# Cuong_Dao_Clock_Led7_23.net
KiCad netlist of a schematic drawn in Altium Designer
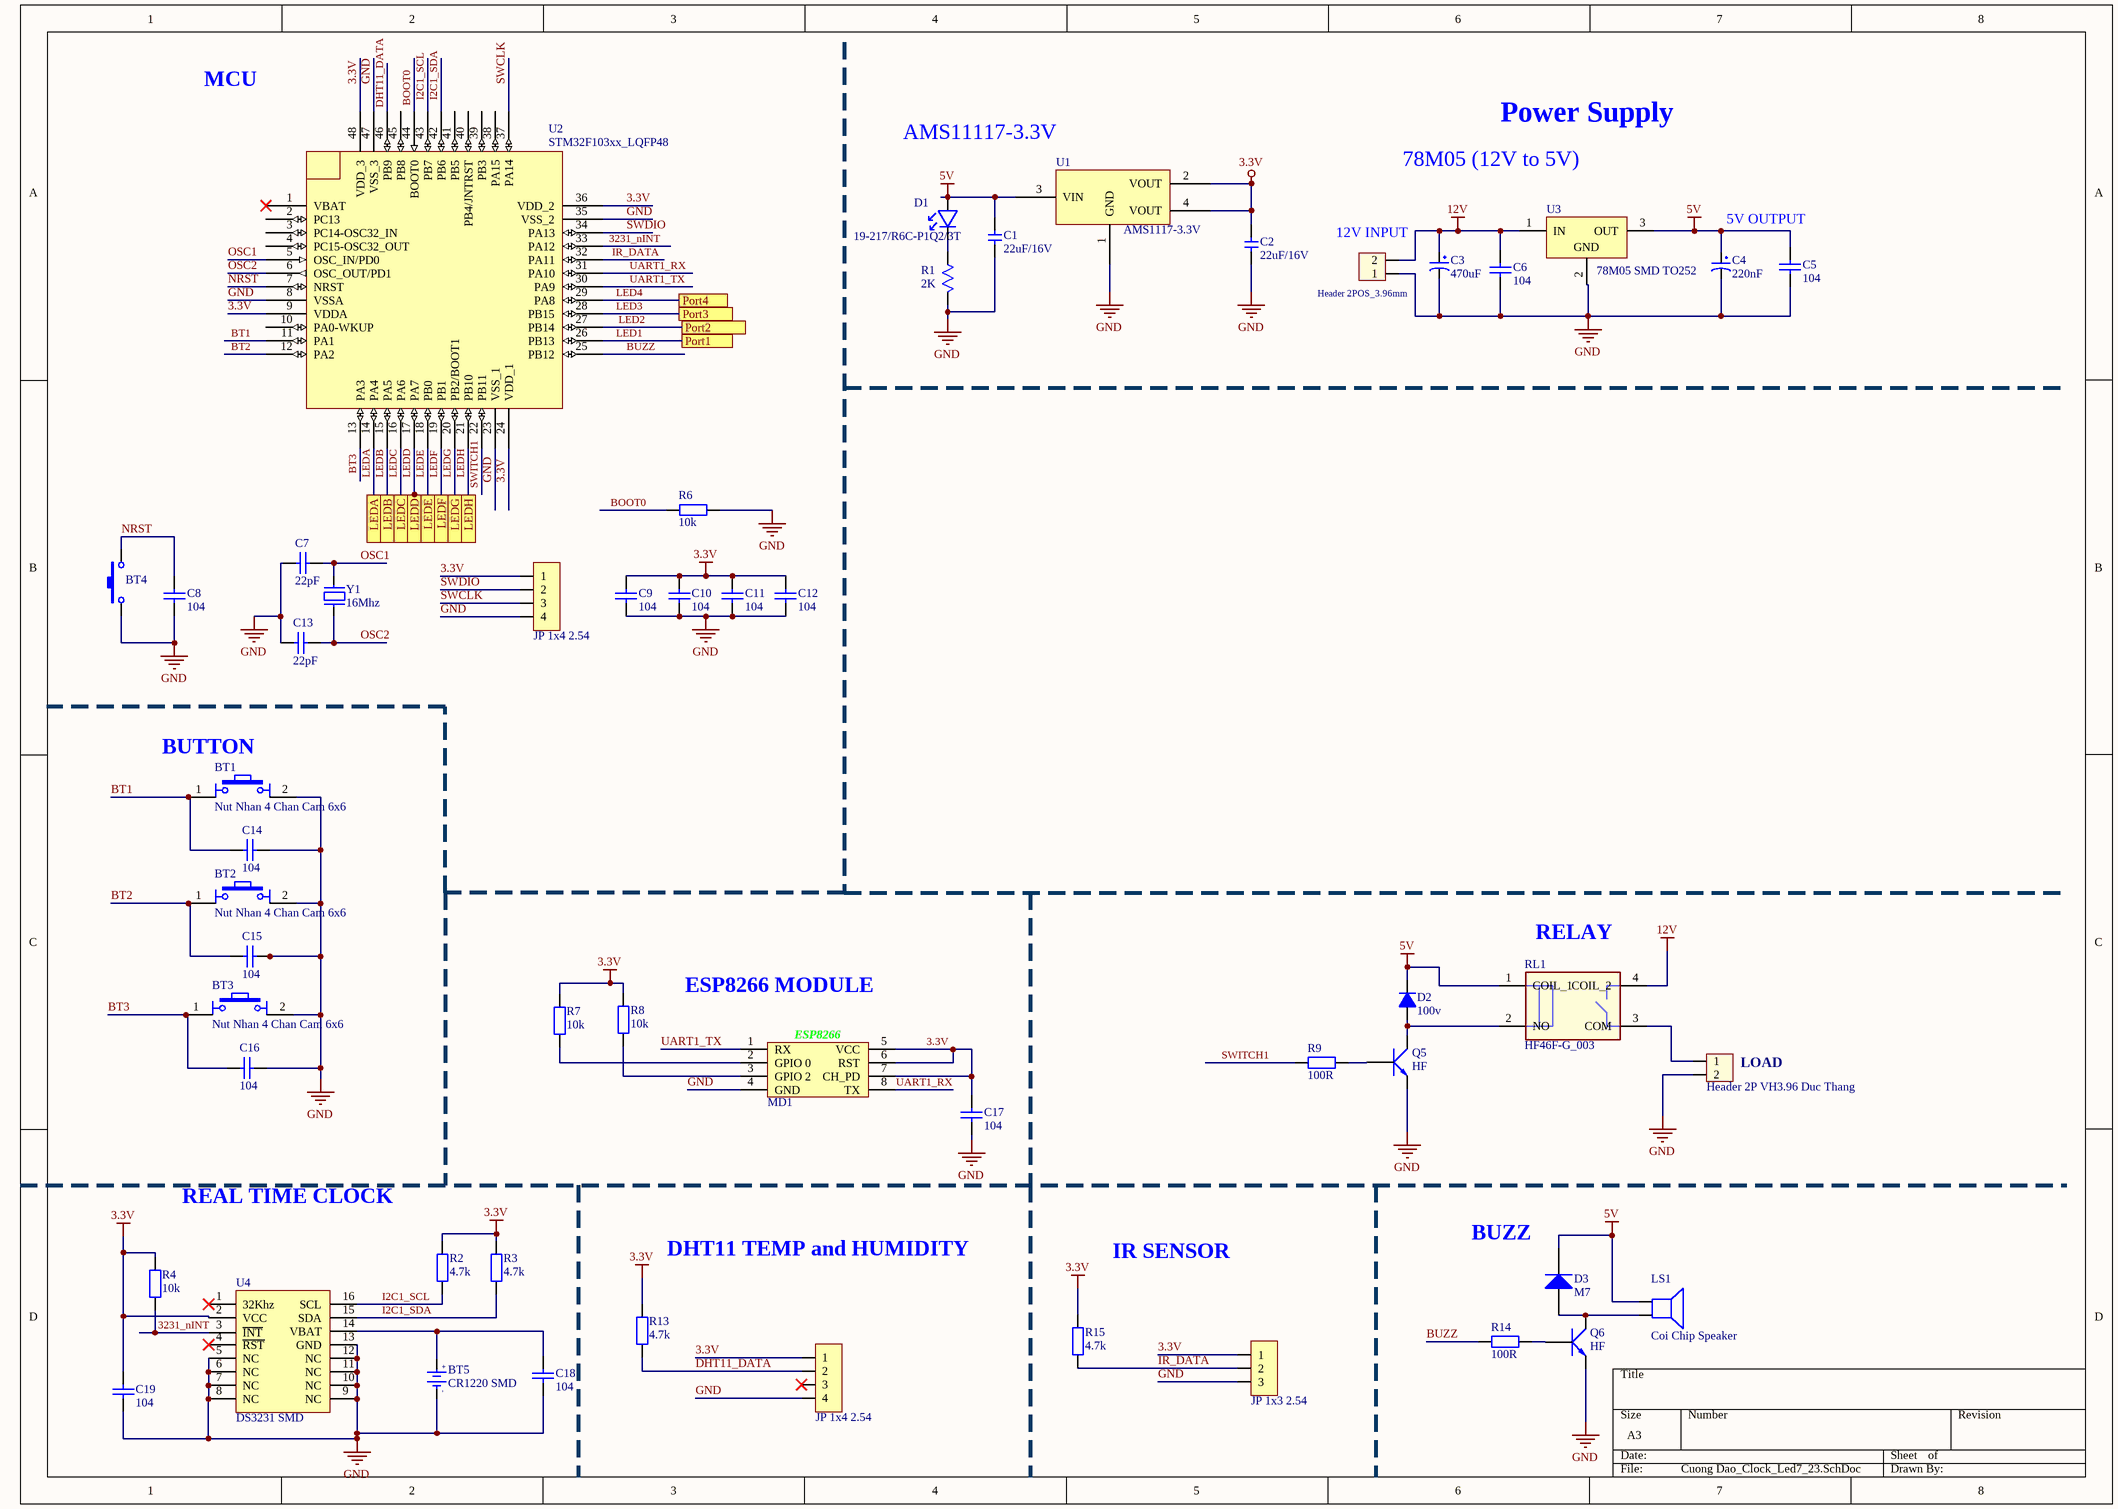
[diagram p0: Cuong Dao_Clock_Led7_23.SchDoc]

(export (version "E")
  (design (tool "Eeschema 10.0.6"))
  (components
    (comp (ref "BT1")
      (value "Nut Nhan 4 Chan Cam 6x6")
      (footprint "Nut Nhan 4 Chan Cam 6x6")
      (description "Nut Nhan 4 Chan 6x6mm")
      (libsource (lib "Altium_Lib_by_KhueNguyenCreator") (part "Nut Nhan 4 Chan Cam 6x6"))
    )
    (comp (ref "BT2")
      (value "Nut Nhan 4 Chan Cam 6x6")
      (footprint "Nut Nhan 4 Chan Cam 6x6")
      (description "Nut Nhan 4 Chan 6x6mm")
      (libsource (lib "Altium_Lib_by_KhueNguyenCreator") (part "Nut Nhan 4 Chan Cam 6x6"))
    )
    (comp (ref "BT3")
      (value "Nut Nhan 4 Chan Cam 6x6")
      (footprint "Nut Nhan 4 Chan Cam 6x6")
      (description "Nut Nhan 4 Chan 6x6mm")
      (libsource (lib "Altium_Lib_by_KhueNguyenCreator") (part "Nut Nhan 4 Chan Cam 6x6"))
    )
    (comp (ref "BT4")
      (value "Nut Nhan 2 Chan SMD 3x6x2.5")
      (footprint "Nut Nhan 2 Chan SMD 3x6x2.5")
      (libsource (lib "Altium_Lib_by_KhueNguyenCreator") (part "Nut Nhan 2 Chan SMD 3x6x2.5"))
    )
    (comp (ref "BT5")
      (value "CR1220 SMD")
      (footprint "DE PIN CR1220")
      (libsource (lib "Altium_Lib_by_KhueNguyenCreator") (part "De pin CR1220 SMD"))
    )
    (comp (ref "C1")
      (value "22uF/16V")
      (footprint "C0603")
      (description "Multilayer Ceramic Capacitors MLCC, SMD/SMT 22uF, 16V, 10%, 0603")
      (libsource (lib "ECA_FAE_Hardware Engineering") (part "C0603"))
    )
    (comp (ref "C2")
      (value "22uF/16V")
      (footprint "C0603")
      (description "Multilayer Ceramic Capacitors MLCC, SMD/SMT 22uF, 16V, 10%, 0603")
      (libsource (lib "ECA_FAE_Hardware Engineering") (part "C0603"))
    )
    (comp (ref "C3")
      (value "470uF")
      (footprint "tu hoa 10mm")
      (description "Cắm")
      (libsource (lib "Altium_Lib_by_KhueNguyenCreator") (part "Tu Hoa 470uF 35V 10x15"))
    )
    (comp (ref "C4")
      (value "220nF")
      (footprint "tu hoa 8mm")
      (description "Cắm")
      (libsource (lib "Altium_Lib_by_KhueNguyenCreator") (part "Tu Hoa 220uF 35V 8x12"))
    )
    (comp (ref "C5")
      (value "104")
      (footprint "tu 1206")
      (description "Dán")
      (libsource (lib "Altium_Lib_by_KhueNguyenCreator") (part "Tu 1206 104 50V 20%"))
    )
    (comp (ref "C6")
      (value "104")
      (footprint "tu 1206")
      (description "Dán")
      (libsource (lib "Altium_Lib_by_KhueNguyenCreator") (part "Tu 1206 104 50V 20%"))
    )
    (comp (ref "C7")
      (value "22pF")
      (footprint "tu 0805")
      (description "Dán")
      (libsource (lib "Altium_Lib_by_KhueNguyenCreator") (part "Tu 0805 22pF 50V 10%"))
    )
    (comp (ref "C8")
      (value "104")
      (footprint "tu 0805")
      (description "Dán")
      (libsource (lib "Altium_Lib_by_KhueNguyenCreator") (part "Tu 0805 104 50V 10%"))
    )
    (comp (ref "C9")
      (value "104")
      (footprint "tu 0805")
      (description "Dán")
      (libsource (lib "Altium_Lib_by_KhueNguyenCreator") (part "Tu 0805 104 50V 10%"))
    )
    (comp (ref "C10")
      (value "104")
      (footprint "tu 0805")
      (description "Dán")
      (libsource (lib "Altium_Lib_by_KhueNguyenCreator") (part "Tu 0805 104 50V 10%"))
    )
    (comp (ref "C11")
      (value "104")
      (footprint "tu 0805")
      (description "Dán")
      (libsource (lib "Altium_Lib_by_KhueNguyenCreator") (part "Tu 0805 104 50V 10%"))
    )
    (comp (ref "C12")
      (value "104")
      (footprint "tu 0805")
      (description "Dán")
      (libsource (lib "Altium_Lib_by_KhueNguyenCreator") (part "Tu 0805 104 50V 10%"))
    )
    (comp (ref "C13")
      (value "22pF")
      (footprint "tu 0805")
      (description "Dán")
      (libsource (lib "Altium_Lib_by_KhueNguyenCreator") (part "Tu 0805 22pF 50V 10%"))
    )
    (comp (ref "C14")
      (value "104")
      (footprint "tu 0805")
      (description "Dán")
      (libsource (lib "Altium_Lib_by_KhueNguyenCreator") (part "Tu 0805 104 50V 10%"))
    )
    (comp (ref "C15")
      (value "104")
      (footprint "tu 0805")
      (description "Dán")
      (libsource (lib "Altium_Lib_by_KhueNguyenCreator") (part "Tu 0805 104 50V 10%"))
    )
    (comp (ref "C16")
      (value "104")
      (footprint "tu 0805")
      (description "Dán")
      (libsource (lib "Altium_Lib_by_KhueNguyenCreator") (part "Tu 0805 104 50V 10%"))
    )
    (comp (ref "C17")
      (value "104")
      (footprint "tu 0805")
      (description "Dán")
      (libsource (lib "Altium_Lib_by_KhueNguyenCreator") (part "Tu 0805 104 50V 10%"))
    )
    (comp (ref "C18")
      (value "104")
      (footprint "tu 0805")
      (description "Dán")
      (libsource (lib "Altium_Lib_by_KhueNguyenCreator") (part "Tu 0805 104 50V 10%"))
    )
    (comp (ref "C19")
      (value "104")
      (footprint "tu 0805")
      (description "Dán")
      (libsource (lib "Altium_Lib_by_KhueNguyenCreator") (part "Tu 0805 104 50V 10%"))
    )
    (comp (ref "D1")
      (value "19-217/R6C-P1Q2/3T")
      (footprint "LED_19-217")
      (description "LED")
      (fields (field (name "PART NUMBER") "19-217/R6C-P1Q2/"))
      (libsource (lib "ICE_Library") (part "LED 19-217"))
    )
    (comp (ref "D2")
      (value "100v")
      (footprint "DIODE 0.5A")
      (description "Cắm")
      (libsource (lib "Altium_Lib_by_KhueNguyenCreator") (part "Diode 1N4148"))
    )
    (comp (ref "D3")
      (value "M7")
      (footprint "DIODE SMA")
      (description "Dán")
      (libsource (lib "Altium_Lib_by_KhueNguyenCreator") (part "Diode M7 ( 4007 )"))
    )
    (comp (ref "H1")
      (value "Header 2POS_3.96mm")
      (footprint "VH3.96M-2")
      (description "Cắm")
      (libsource (lib "Altium_Lib_by_KhueNguyenCreator") (part "Header 2P VH3.96 Duc Thang"))
    )
    (comp (ref "H2")
      (value "Header 2P VH3.96 Duc Thang")
      (footprint "VH3.96M-2")
      (description "Cắm")
      (libsource (lib "") (part "Header 2P VH3.96 Duc Thang_1"))
    )
    (comp (ref "JP1")
      (value "JP 1x4 2.54")
      (footprint "JP 1x4 DT")
      (description "Cắm")
      (libsource (lib "Altium_Lib_by_KhueNguyenCreator") (part "JP 1x4 2.54 Duc Thang"))
    )
    (comp (ref "JP2")
      (value "JP 1x3 2.54")
      (footprint "JP 1x3 CT")
      (description "Cắm")
      (libsource (lib "Altium_Lib_by_KhueNguyenCreator") (part "JP 1x3 2.54 Cai Thang"))
    )
    (comp (ref "JP3")
      (value "JP 1x4 2.54")
      (footprint "JP 1x4 CT")
      (description "Cắm")
      (libsource (lib "Altium_Lib_by_KhueNguyenCreator") (part "JP 1x4 2.54 Cai Thang"))
    )
    (comp (ref "LS1")
      (value "Coi Chip Speaker")
      (footprint "Coi Chip Speacker")
      (description "Còi chip")
      (libsource (lib "Altium_Lib_by_KhueNguyenCreator") (part "Coi Chip Speaker"))
    )
    (comp (ref "MD1")
      (value "ESP8266 Module")
      (footprint "ESP2866 Module")
      (libsource (lib "Altium_Lib_by_KhueNguyenCreator") (part "ESP8266 Module"))
    )
    (comp (ref "Q5")
      (value "HF")
      (footprint "SOT23")
      (description "NPN transistor")
      (libsource (lib "Altium_Lib_by_KhueNguyenCreator") (part "C1815 HF SMD"))
    )
    (comp (ref "Q6")
      (value "HF")
      (footprint "SOT23")
      (description "NPN transistor")
      (libsource (lib "Altium_Lib_by_KhueNguyenCreator") (part "C1815 HF SMD"))
    )
    (comp (ref "R1")
      (value "2K")
      (footprint "RES0603")
      (description "Chip Resistor - Surface Mount 2KΩ ±1% 1/16W 0603 RoHS")
      (libsource (lib "ECA_FAE_Hardware Engineering") (part "R0603"))
    )
    (comp (ref "R2")
      (value "4.7k")
      (footprint "tro smd 0805")
      (description "Dán")
      (libsource (lib "Altium_Lib_by_KhueNguyenCreator") (part "Tro 0805 5% 4.7k"))
    )
    (comp (ref "R3")
      (value "4.7k")
      (footprint "tro smd 0805")
      (description "Dán")
      (libsource (lib "Altium_Lib_by_KhueNguyenCreator") (part "Tro 0805 5% 4.7k"))
    )
    (comp (ref "R4")
      (value "10k")
      (footprint "tro smd 0805")
      (description "Dán")
      (libsource (lib "Altium_Lib_by_KhueNguyenCreator") (part "Tro 0805 5% 10k"))
    )
    (comp (ref "R6")
      (value "10k")
      (footprint "tro smd 0805")
      (description "Dán")
      (libsource (lib "Altium_Lib_by_KhueNguyenCreator") (part "Tro 0805 5% 10k"))
    )
    (comp (ref "R7")
      (value "10k")
      (footprint "tro smd 0805")
      (description "Dán")
      (libsource (lib "Altium_Lib_by_KhueNguyenCreator") (part "Tro 0805 5% 10k"))
    )
    (comp (ref "R8")
      (value "10k")
      (footprint "tro smd 0805")
      (description "Dán")
      (libsource (lib "Altium_Lib_by_KhueNguyenCreator") (part "Tro 0805 5% 10k"))
    )
    (comp (ref "R9")
      (value "100R")
      (footprint "tro smd 0805")
      (description "Dán")
      (libsource (lib "Altium_Lib_by_KhueNguyenCreator") (part "Tro 0805 5% 100R"))
    )
    (comp (ref "R13")
      (value "4.7k")
      (footprint "tro smd 0805")
      (description "Dán")
      (libsource (lib "Altium_Lib_by_KhueNguyenCreator") (part "Tro 0805 5% 4.7k"))
    )
    (comp (ref "R14")
      (value "100R")
      (footprint "tro smd 0805")
      (description "Dán")
      (libsource (lib "Altium_Lib_by_KhueNguyenCreator") (part "Tro 0805 5% 100R"))
    )
    (comp (ref "R15")
      (value "4.7k")
      (footprint "tro smd 0805")
      (description "Dán")
      (libsource (lib "Altium_Lib_by_KhueNguyenCreator") (part "Tro 0805 5% 4.7k"))
    )
    (comp (ref "RL1")
      (value "HF46F-G_003")
      (footprint "HF46F012HS1F610")
      (description "HF46F-G_003-HS1F_610_")
      (fields (field (name "MFR") "Hongfa") (field (name "PART NUMBER") "HF46F-G/003-HS1F(610)"))
      (libsource (lib "ECA_FAE_Hardware Engineering") (part "Relay_HF46F"))
    )
    (comp (ref "U1")
      (value "AMS1117-3.3V")
      (footprint "SOT223")
      (description "SMD LDO regulator")
      (fields (field (name "MFR") "Advanced Monolithic System"))
      (libsource (lib "Altium_Lib_by_KhueNguyenCreator") (part "AMS1117 SMD"))
    )
    (comp (ref "U2")
      (value "STM32F103xx_LQFP48")
      (footprint "STM32_LQPF48")
      (fields (field (name "PUBLISHER") "Altium Limited"))
      (libsource (lib "Altium_Lib_by_KhueNguyenCreator") (part "STM32F103xx_LQFP48"))
    )
    (comp (ref "U3")
      (value "78M05 SMD TO252")
      (footprint "TO252")
      (description "Dán")
      (libsource (lib "Altium_Lib_by_KhueNguyenCreator") (part "78M05 SMD TO252"))
    )
    (comp (ref "U4")
      (value "DS3231 SMD")
      (footprint "SOIC 16")
      (description "SOIC")
      (libsource (lib "Altium_Lib_by_KhueNguyenCreator") (part "DS3231 SMD"))
    )
    (comp (ref "Y1")
      (value "16Mhz")
      (footprint "Thach Anh 2 chan SMD")
      (description "Crystal For all Crystal 2pin.")
      (libsource (lib "Altium_Lib_by_KhueNguyenCreator") (part "Thach Anh 2 chan SMD"))
    )
  )
  (nets
    (net (code "1") (name "/3231_nINT") (class "Default")
      (node (ref "R4") (pin "1") (pinfunction "1_1") (pintype "passive"))
      (node (ref "U2") (pin "33") (pinfunction "PA12_33") (pintype "bidirectional"))
      (node (ref "U4") (pin "3") (pinfunction "~{INT}_3") (pintype "power_in"))
    )
    (net (code "2") (name "/BOOT0") (class "Default")
      (node (ref "R6") (pin "2") (pinfunction "2_2") (pintype "passive"))
      (node (ref "U2") (pin "44") (pinfunction "BOOT0_44") (pintype "input"))
    )
    (net (code "3") (name "/BT1") (class "Default")
      (node (ref "BT1") (pin "1") (pintype "passive"))
      (node (ref "C14") (pin "1") (pinfunction "1_1") (pintype "passive"))
      (node (ref "U2") (pin "11") (pinfunction "PA1_11") (pintype "bidirectional"))
    )
    (net (code "4") (name "/BT2") (class "Default")
      (node (ref "BT2") (pin "1") (pintype "passive"))
      (node (ref "C15") (pin "1") (pinfunction "1_1") (pintype "passive"))
      (node (ref "U2") (pin "12") (pinfunction "PA2_12") (pintype "bidirectional"))
    )
    (net (code "5") (name "/BT3") (class "Default")
      (node (ref "BT3") (pin "1") (pintype "passive"))
      (node (ref "C16") (pin "1") (pinfunction "1_1") (pintype "passive"))
      (node (ref "U2") (pin "13") (pinfunction "PA3_13") (pintype "bidirectional"))
    )
    (net (code "6") (name "/BUZZ") (class "Default")
      (node (ref "R14") (pin "1") (pinfunction "1_1") (pintype "passive"))
      (node (ref "U2") (pin "25") (pinfunction "PB12_25") (pintype "bidirectional"))
    )
    (net (code "7") (name "/DHT11_DATA") (class "Default")
      (node (ref "JP3") (pin "2") (pinfunction "2_2") (pintype "passive"))
      (node (ref "R13") (pin "1") (pinfunction "1_1") (pintype "passive"))
      (node (ref "U2") (pin "46") (pinfunction "PB9_46") (pintype "bidirectional"))
    )
    (net (code "8") (name "/I2C1_SCL") (class "Default")
      (node (ref "R2") (pin "1") (pinfunction "1_1") (pintype "passive"))
      (node (ref "U2") (pin "43") (pinfunction "PB7_43") (pintype "bidirectional"))
      (node (ref "U4") (pin "16") (pinfunction "SCL_16") (pintype "power_in"))
    )
    (net (code "9") (name "/I2C1_SDA") (class "Default")
      (node (ref "R3") (pin "1") (pinfunction "1_1") (pintype "passive"))
      (node (ref "U2") (pin "42") (pinfunction "PB6_42") (pintype "bidirectional"))
      (node (ref "U4") (pin "15") (pinfunction "SDA_15") (pintype "power_in"))
    )
    (net (code "10") (name "/IR_DATA") (class "Default")
      (node (ref "JP2") (pin "2") (pinfunction "2_2") (pintype "passive"))
      (node (ref "R15") (pin "1") (pinfunction "1_1") (pintype "passive"))
      (node (ref "U2") (pin "32") (pinfunction "PA11_32") (pintype "bidirectional"))
    )
    (net (code "11") (name "/LED1") (class "Default")
      (node (ref "U2") (pin "26") (pinfunction "PB13_26") (pintype "bidirectional"))
    )
    (net (code "12") (name "/LED2") (class "Default")
      (node (ref "U2") (pin "27") (pinfunction "PB14_27") (pintype "bidirectional"))
    )
    (net (code "13") (name "/LED3") (class "Default")
      (node (ref "U2") (pin "28") (pinfunction "PB15_28") (pintype "bidirectional"))
    )
    (net (code "14") (name "/LED4") (class "Default")
      (node (ref "U2") (pin "29") (pinfunction "PA8_29") (pintype "bidirectional"))
    )
    (net (code "15") (name "/LEDA") (class "Default")
      (node (ref "U2") (pin "14") (pinfunction "PA4_14") (pintype "bidirectional"))
    )
    (net (code "16") (name "/LEDB") (class "Default")
      (node (ref "U2") (pin "15") (pinfunction "PA5_15") (pintype "bidirectional"))
    )
    (net (code "17") (name "/LEDC") (class "Default")
      (node (ref "U2") (pin "16") (pinfunction "PA6_16") (pintype "bidirectional"))
    )
    (net (code "18") (name "/LEDD") (class "Default")
      (node (ref "U2") (pin "17") (pinfunction "PA7_17") (pintype "bidirectional"))
    )
    (net (code "19") (name "/LEDE") (class "Default")
      (node (ref "U2") (pin "18") (pinfunction "PB0_18") (pintype "bidirectional"))
    )
    (net (code "20") (name "/LEDF") (class "Default")
      (node (ref "U2") (pin "19") (pinfunction "PB1_19") (pintype "bidirectional"))
    )
    (net (code "21") (name "/LEDG") (class "Default")
      (node (ref "U2") (pin "20") (pinfunction "PB2/BOOT1_20") (pintype "bidirectional"))
    )
    (net (code "22") (name "/LEDH") (class "Default")
      (node (ref "U2") (pin "21") (pinfunction "PB10_21") (pintype "bidirectional"))
    )
    (net (code "23") (name "/NRST") (class "Default")
      (node (ref "BT4") (pin "2") (pinfunction "2_2") (pintype "passive"))
      (node (ref "C8") (pin "1") (pinfunction "1_1") (pintype "passive"))
      (node (ref "U2") (pin "7") (pinfunction "NRST_7") (pintype "bidirectional"))
    )
    (net (code "24") (name "/OSC1") (class "Default")
      (node (ref "C7") (pin "1") (pinfunction "1_1") (pintype "passive"))
      (node (ref "U2") (pin "5") (pinfunction "OSC_IN/PD0_5") (pintype "input"))
      (node (ref "Y1") (pin "2") (pinfunction "2_2") (pintype "passive"))
    )
    (net (code "25") (name "/OSC2") (class "Default")
      (node (ref "C13") (pin "2") (pinfunction "2_2") (pintype "passive"))
      (node (ref "U2") (pin "6") (pinfunction "OSC_OUT/PD1_6") (pintype "output"))
      (node (ref "Y1") (pin "1") (pinfunction "1_1") (pintype "passive"))
    )
    (net (code "26") (name "/SWCLK") (class "Default")
      (node (ref "JP1") (pin "3") (pinfunction "3_3") (pintype "passive"))
      (node (ref "U2") (pin "37") (pinfunction "PA14_37") (pintype "bidirectional"))
    )
    (net (code "27") (name "/SWDIO") (class "Default")
      (node (ref "JP1") (pin "2") (pinfunction "2_2") (pintype "passive"))
      (node (ref "U2") (pin "34") (pinfunction "PA13_34") (pintype "bidirectional"))
    )
    (net (code "28") (name "/SWITCH1") (class "Default")
      (node (ref "R9") (pin "1") (pinfunction "1_1") (pintype "passive"))
      (node (ref "U2") (pin "22") (pinfunction "PB11_22") (pintype "bidirectional"))
    )
    (net (code "29") (name "/UART1_RX") (class "Default")
      (node (ref "MD1") (pin "8") (pinfunction "TX_8") (pintype "passive"))
      (node (ref "U2") (pin "31") (pinfunction "PA10_31") (pintype "bidirectional"))
    )
    (net (code "30") (name "/UART1_TX") (class "Default")
      (node (ref "MD1") (pin "1") (pinfunction "RX_1") (pintype "passive"))
      (node (ref "U2") (pin "30") (pinfunction "PA9_30") (pintype "bidirectional"))
    )
    (net (code "31") (name "3.3V") (class "Default")
      (node (ref "C10") (pin "1") (pinfunction "1_1") (pintype "passive"))
      (node (ref "C11") (pin "1") (pinfunction "1_1") (pintype "passive"))
      (node (ref "C12") (pin "1") (pinfunction "1_1") (pintype "passive"))
      (node (ref "C17") (pin "2") (pinfunction "2_2") (pintype "passive"))
      (node (ref "C19") (pin "2") (pinfunction "2_2") (pintype "passive"))
      (node (ref "C2") (pin "1") (pinfunction "1_1") (pintype "passive"))
      (node (ref "C9") (pin "1") (pinfunction "1_1") (pintype "passive"))
      (node (ref "JP1") (pin "1") (pinfunction "1_1") (pintype "passive"))
      (node (ref "JP2") (pin "1") (pinfunction "1_1") (pintype "passive"))
      (node (ref "JP3") (pin "1") (pinfunction "1_1") (pintype "passive"))
      (node (ref "MD1") (pin "5") (pinfunction "VCC_5") (pintype "passive"))
      (node (ref "MD1") (pin "6") (pinfunction "RST_6") (pintype "passive"))
      (node (ref "MD1") (pin "7") (pinfunction "CH_PD_7") (pintype "passive"))
      (node (ref "R13") (pin "2") (pinfunction "2_2") (pintype "passive"))
      (node (ref "R15") (pin "2") (pinfunction "2_2") (pintype "passive"))
      (node (ref "R2") (pin "2") (pinfunction "2_2") (pintype "passive"))
      (node (ref "R3") (pin "2") (pinfunction "2_2") (pintype "passive"))
      (node (ref "R4") (pin "2") (pinfunction "2_2") (pintype "passive"))
      (node (ref "R7") (pin "1") (pinfunction "1_1") (pintype "passive"))
      (node (ref "R8") (pin "2") (pinfunction "2_2") (pintype "passive"))
      (node (ref "U1") (pin "2") (pinfunction "VOUT_2") (pintype "passive"))
      (node (ref "U1") (pin "4") (pinfunction "VOUT_4") (pintype "passive"))
      (node (ref "U2") (pin "24") (pinfunction "VDD_1_24") (pintype "power_in"))
      (node (ref "U2") (pin "36") (pinfunction "VDD_2_36") (pintype "power_in"))
      (node (ref "U2") (pin "48") (pinfunction "VDD_3_48") (pintype "power_in"))
      (node (ref "U2") (pin "9") (pinfunction "VDDA_9") (pintype "power_in"))
      (node (ref "U4") (pin "2") (pinfunction "VCC_2") (pintype "power_in"))
    )
    (net (code "32") (name "5V") (class "Default")
      (node (ref "C1") (pin "1") (pinfunction "1_1") (pintype "passive"))
      (node (ref "C4") (pin "1") (pinfunction "1_1") (pintype "passive"))
      (node (ref "C5") (pin "1") (pinfunction "1_1") (pintype "passive"))
      (node (ref "D1") (pin "2") (pinfunction "A_2") (pintype "passive"))
      (node (ref "D2") (pin "2") (pinfunction "K_2") (pintype "passive"))
      (node (ref "D3") (pin "2") (pinfunction "K_2") (pintype "passive"))
      (node (ref "LS1") (pin "1") (pinfunction "1_1") (pintype "passive"))
      (node (ref "RL1") (pin "1") (pinfunction "COIL_1_1") (pintype "passive"))
      (node (ref "U1") (pin "3") (pinfunction "VIN_3") (pintype "passive"))
      (node (ref "U3") (pin "3") (pinfunction "OUT_3") (pintype "power_in"))
    )
    (net (code "33") (name "12V") (class "Default")
      (node (ref "C3") (pin "1") (pinfunction "1_1") (pintype "passive"))
      (node (ref "C6") (pin "1") (pinfunction "1_1") (pintype "passive"))
      (node (ref "H1") (pin "2") (pinfunction "2_2") (pintype "passive"))
      (node (ref "RL1") (pin "4") (pinfunction "COIL_2_4") (pintype "passive"))
      (node (ref "U3") (pin "1") (pinfunction "IN_1") (pintype "power_in"))
    )
    (net (code "34") (name "GND") (class "Default")
      (node (ref "BT1") (pin "2") (pintype "passive"))
      (node (ref "BT2") (pin "2") (pintype "passive"))
      (node (ref "BT3") (pin "2") (pintype "passive"))
      (node (ref "BT4") (pin "1") (pinfunction "1_1") (pintype "passive"))
      (node (ref "BT5") (pin "2") (pinfunction "GND_2") (pintype "passive"))
      (node (ref "C1") (pin "2") (pinfunction "2_2") (pintype "passive"))
      (node (ref "C10") (pin "2") (pinfunction "2_2") (pintype "passive"))
      (node (ref "C11") (pin "2") (pinfunction "2_2") (pintype "passive"))
      (node (ref "C12") (pin "2") (pinfunction "2_2") (pintype "passive"))
      (node (ref "C13") (pin "1") (pinfunction "1_1") (pintype "passive"))
      (node (ref "C14") (pin "2") (pinfunction "2_2") (pintype "passive"))
      (node (ref "C15") (pin "2") (pinfunction "2_2") (pintype "passive"))
      (node (ref "C16") (pin "2") (pinfunction "2_2") (pintype "passive"))
      (node (ref "C17") (pin "1") (pinfunction "1_1") (pintype "passive"))
      (node (ref "C18") (pin "1") (pinfunction "1_1") (pintype "passive"))
      (node (ref "C19") (pin "1") (pinfunction "1_1") (pintype "passive"))
      (node (ref "C2") (pin "2") (pinfunction "2_2") (pintype "passive"))
      (node (ref "C3") (pin "2") (pinfunction "2_2") (pintype "passive"))
      (node (ref "C4") (pin "2") (pinfunction "2_2") (pintype "passive"))
      (node (ref "C5") (pin "2") (pinfunction "2_2") (pintype "passive"))
      (node (ref "C6") (pin "2") (pinfunction "2_2") (pintype "passive"))
      (node (ref "C7") (pin "2") (pinfunction "2_2") (pintype "passive"))
      (node (ref "C8") (pin "2") (pinfunction "2_2") (pintype "passive"))
      (node (ref "C9") (pin "2") (pinfunction "2_2") (pintype "passive"))
      (node (ref "H1") (pin "1") (pinfunction "1_1") (pintype "passive"))
      (node (ref "H2") (pin "2") (pinfunction "2_2") (pintype "passive"))
      (node (ref "JP1") (pin "4") (pinfunction "4_4") (pintype "passive"))
      (node (ref "JP2") (pin "3") (pinfunction "3_3") (pintype "passive"))
      (node (ref "JP3") (pin "4") (pinfunction "4_4") (pintype "passive"))
      (node (ref "MD1") (pin "4") (pinfunction "GND_4") (pintype "passive"))
      (node (ref "Q5") (pin "2") (pinfunction "E_2") (pintype "passive"))
      (node (ref "Q6") (pin "2") (pinfunction "E_2") (pintype "passive"))
      (node (ref "R1") (pin "2") (pinfunction "2_2") (pintype "passive"))
      (node (ref "R6") (pin "1") (pinfunction "1_1") (pintype "passive"))
      (node (ref "U1") (pin "1") (pinfunction "GND_1") (pintype "passive"))
      (node (ref "U2") (pin "23") (pinfunction "VSS_1_23") (pintype "power_in"))
      (node (ref "U2") (pin "35") (pinfunction "VSS_2_35") (pintype "power_in"))
      (node (ref "U2") (pin "47") (pinfunction "VSS_3_47") (pintype "power_in"))
      (node (ref "U2") (pin "8") (pinfunction "VSSA_8") (pintype "power_in"))
      (node (ref "U3") (pin "2") (pinfunction "GND_2") (pintype "power_in"))
      (node (ref "U4") (pin "10") (pinfunction "NC_10") (pintype "power_in"))
      (node (ref "U4") (pin "11") (pinfunction "NC_11") (pintype "power_in"))
      (node (ref "U4") (pin "12") (pinfunction "NC_12") (pintype "power_in"))
      (node (ref "U4") (pin "13") (pinfunction "GND_13") (pintype "power_in"))
      (node (ref "U4") (pin "5") (pinfunction "NC_5") (pintype "power_in"))
      (node (ref "U4") (pin "6") (pinfunction "NC_6") (pintype "power_in"))
      (node (ref "U4") (pin "7") (pinfunction "NC_7") (pintype "power_in"))
      (node (ref "U4") (pin "8") (pinfunction "NC_8") (pintype "power_in"))
      (node (ref "U4") (pin "9") (pinfunction "NC_9") (pintype "power_in"))
    )
    (net (code "35") (name "Net-(BT5-+3V)") (class "Default")
      (node (ref "BT5") (pin "1") (pinfunction "+3V_1") (pintype "passive"))
      (node (ref "C18") (pin "2") (pinfunction "2_2") (pintype "passive"))
      (node (ref "U4") (pin "14") (pinfunction "VBAT_14") (pintype "power_in"))
    )
    (net (code "36") (name "Net-(D1-K)") (class "Default")
      (node (ref "D1") (pin "1") (pinfunction "K_1") (pintype "passive"))
      (node (ref "R1") (pin "1") (pinfunction "1_1") (pintype "passive"))
    )
    (net (code "37") (name "Net-(D2-A)") (class "Default")
      (node (ref "D2") (pin "1") (pinfunction "A_1") (pintype "passive"))
      (node (ref "Q5") (pin "3") (pinfunction "C_3") (pintype "passive"))
      (node (ref "RL1") (pin "2") (pinfunction "NO_2") (pintype "passive"))
    )
    (net (code "38") (name "Net-(D3-A)") (class "Default")
      (node (ref "D3") (pin "1") (pinfunction "A_1") (pintype "passive"))
      (node (ref "LS1") (pin "2") (pinfunction "2_2") (pintype "passive"))
      (node (ref "Q6") (pin "3") (pinfunction "C_3") (pintype "passive"))
    )
    (net (code "39") (name "Net-(MD1-GPIO_0)") (class "Default")
      (node (ref "MD1") (pin "2") (pinfunction "GPIO_0_2") (pintype "passive"))
      (node (ref "R7") (pin "2") (pinfunction "2_2") (pintype "passive"))
    )
    (net (code "40") (name "Net-(MD1-GPIO_2)") (class "Default")
      (node (ref "MD1") (pin "3") (pinfunction "GPIO_2_3") (pintype "passive"))
      (node (ref "R8") (pin "1") (pinfunction "1_1") (pintype "passive"))
    )
    (net (code "41") (name "Net-(Q5-B)") (class "Default")
      (node (ref "Q5") (pin "1") (pinfunction "B_1") (pintype "passive"))
      (node (ref "R9") (pin "2") (pinfunction "2_2") (pintype "passive"))
    )
    (net (code "42") (name "Net-(Q6-B)") (class "Default")
      (node (ref "Q6") (pin "1") (pinfunction "B_1") (pintype "passive"))
      (node (ref "R14") (pin "2") (pinfunction "2_2") (pintype "passive"))
    )
    (net (code "43") (name "Net-(RL1-COM)") (class "Default")
      (node (ref "H2") (pin "1") (pinfunction "1_1") (pintype "passive"))
      (node (ref "RL1") (pin "3") (pinfunction "COM_3") (pintype "passive"))
    )
    (net (code "44") (name "unconnected-(JP3-Pad3)") (class "Default")
      (node (ref "JP3") (pin "3") (pinfunction "3_3") (pintype "passive+no_connect"))
    )
    (net (code "45") (name "unconnected-(U2-PA0-WKUP-Pad10)") (class "Default")
      (node (ref "U2") (pin "10") (pinfunction "PA0-WKUP_10") (pintype "bidirectional"))
    )
    (net (code "46") (name "unconnected-(U2-PA15-Pad38)") (class "Default")
      (node (ref "U2") (pin "38") (pinfunction "PA15_38") (pintype "bidirectional"))
    )
    (net (code "47") (name "unconnected-(U2-PB3-Pad39)") (class "Default")
      (node (ref "U2") (pin "39") (pinfunction "PB3_39") (pintype "bidirectional"))
    )
    (net (code "48") (name "unconnected-(U2-PB4{slash}JNTRST-Pad40)") (class "Default")
      (node (ref "U2") (pin "40") (pinfunction "PB4/JNTRST_40") (pintype "bidirectional"))
    )
    (net (code "49") (name "unconnected-(U2-PB5-Pad41)") (class "Default")
      (node (ref "U2") (pin "41") (pinfunction "PB5_41") (pintype "bidirectional"))
    )
    (net (code "50") (name "unconnected-(U2-PB8-Pad45)") (class "Default")
      (node (ref "U2") (pin "45") (pinfunction "PB8_45") (pintype "bidirectional"))
    )
    (net (code "51") (name "unconnected-(U2-PC13-Pad2)") (class "Default")
      (node (ref "U2") (pin "2") (pinfunction "PC13_2") (pintype "bidirectional"))
    )
    (net (code "52") (name "unconnected-(U2-PC14-OSC32_IN-Pad3)") (class "Default")
      (node (ref "U2") (pin "3") (pinfunction "PC14-OSC32_IN_3") (pintype "bidirectional"))
    )
    (net (code "53") (name "unconnected-(U2-PC15-OSC32_OUT-Pad4)") (class "Default")
      (node (ref "U2") (pin "4") (pinfunction "PC15-OSC32_OUT_4") (pintype "bidirectional"))
    )
    (net (code "54") (name "unconnected-(U2-VBAT-Pad1)") (class "Default")
      (node (ref "U2") (pin "1") (pinfunction "VBAT_1") (pintype "power_in+no_connect"))
    )
    (net (code "55") (name "unconnected-(U4-32Khz-Pad1)") (class "Default")
      (node (ref "U4") (pin "1") (pinfunction "32Khz_1") (pintype "power_in+no_connect"))
    )
    (net (code "56") (name "unconnected-(U4-~{RST}-Pad4)") (class "Default")
      (node (ref "U4") (pin "4") (pinfunction "~{RST}_4") (pintype "power_in+no_connect"))
    )
  )
)
